# stepper_fw_bw_w_switch.net
KiCad netlist of a schematic drawn in EAGLE
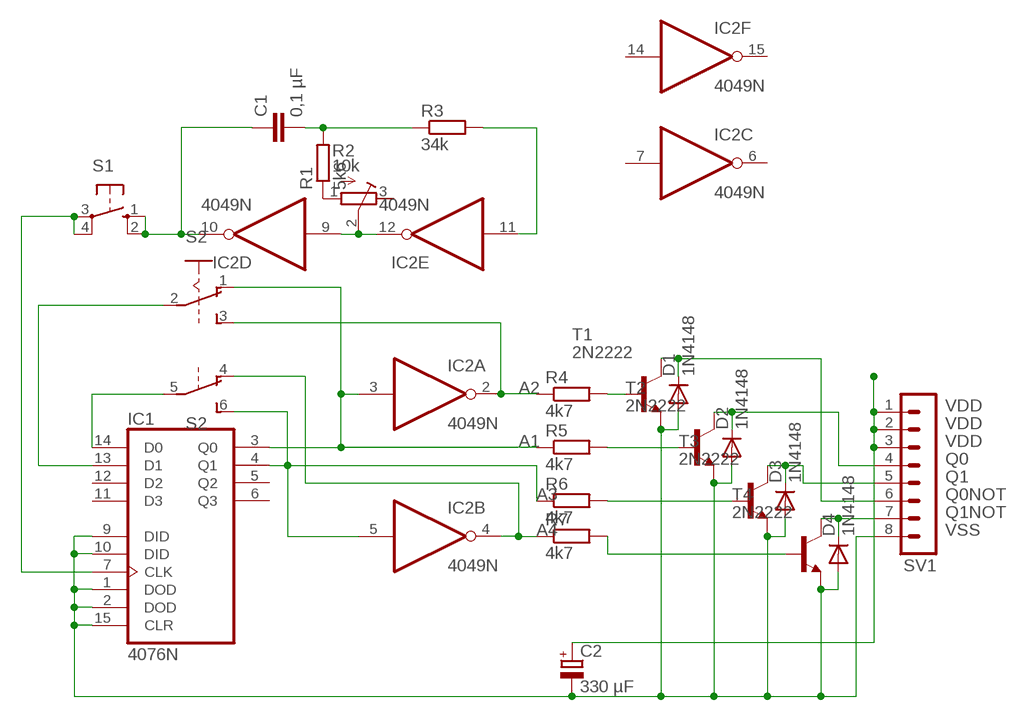
[diagram p0: schematic, sheet 1]

(export (version "E")
  (design (tool "Eeschema 10.0.6"))
  (components
    (comp (ref "C1")
      (value "0,1 µF")
      (footprint "eagle-import:C050-024X044")
      (libsource (lib "eagle-import") (part "C-EU050-024X044"))
    )
    (comp (ref "C2")
      (value "330 µF")
      (footprint "eagle-import:E2,5-5")
      (libsource (lib "eagle-import") (part "CPOL-EUE2.5-5"))
    )
    (comp (ref "D1")
      (value "1N4148")
      (footprint "eagle-import:D-2.5")
      (libsource (lib "eagle-import") (part "DIODE-D-2.5"))
    )
    (comp (ref "D2")
      (value "1N4148")
      (footprint "eagle-import:D-2.5")
      (libsource (lib "eagle-import") (part "DIODE-D-2.5"))
    )
    (comp (ref "D3")
      (value "1N4148")
      (footprint "eagle-import:D-2.5")
      (libsource (lib "eagle-import") (part "DIODE-D-2.5"))
    )
    (comp (ref "D4")
      (value "1N4148")
      (footprint "eagle-import:D-2.5")
      (libsource (lib "eagle-import") (part "DIODE-D-2.5"))
    )
    (comp (ref "IC1")
      (value "4076N")
      (footprint "eagle-import:DIL16")
      (libsource (lib "eagle-import") (part "4076N"))
    )
    (comp (ref "IC2")
      (value "4049N")
      (footprint "eagle-import:DIL16")
      (libsource (lib "eagle-import") (part "4049N"))
    )
    (comp (ref "R1")
      (value "5k6")
      (footprint "eagle-import:0207_10")
      (libsource (lib "eagle-import") (part "R-EU_0207/10"))
    )
    (comp (ref "R2")
      (value "10k")
      (footprint "eagle-import:RTRIM64W")
      (libsource (lib "eagle-import") (part "R-TRIMM64W"))
    )
    (comp (ref "R3")
      (value "34k")
      (footprint "eagle-import:0207_10")
      (libsource (lib "eagle-import") (part "R-EU_0207/10"))
    )
    (comp (ref "R4")
      (value "4k7")
      (footprint "eagle-import:0207_10")
      (libsource (lib "eagle-import") (part "R-EU_0207/10"))
    )
    (comp (ref "R5")
      (value "4k7")
      (footprint "eagle-import:0207_10")
      (libsource (lib "eagle-import") (part "R-EU_0207/10"))
    )
    (comp (ref "R6")
      (value "4k7")
      (footprint "eagle-import:0207_10")
      (libsource (lib "eagle-import") (part "R-EU_0207/10"))
    )
    (comp (ref "R7")
      (value "4k7")
      (footprint "eagle-import:0207_10")
      (libsource (lib "eagle-import") (part "R-EU_0207/10"))
    )
    (comp (ref "S1")
      (value "40-XX")
      (footprint "eagle-import:B3F-40XX")
      (fields (field (name "MF") "OMRON COMPONENTS USA") (field (name "MPN") "B3F-4000"))
      (libsource (lib "eagle-import") (part "40-XX"))
    )
    (comp (ref "S2")
      (value "A68-A31")
      (footprint "eagle-import:A68-A31")
      (libsource (lib "eagle-import") (part "A68-A31"))
    )
    (comp (ref "SV1")
      (value "MA08-1")
      (footprint "eagle-import:MA08-1")
      (libsource (lib "eagle-import") (part "MA08-1"))
    )
    (comp (ref "T1")
      (value "2N2222")
      (footprint "eagle-import:TO18")
      (libsource (lib "eagle-import") (part "2N2222"))
    )
    (comp (ref "T2")
      (value "2N2222")
      (footprint "eagle-import:TO18")
      (libsource (lib "eagle-import") (part "2N2222"))
    )
    (comp (ref "T3")
      (value "2N2222")
      (footprint "eagle-import:TO18")
      (libsource (lib "eagle-import") (part "2N2222"))
    )
    (comp (ref "T4")
      (value "2N2222")
      (footprint "eagle-import:TO18")
      (libsource (lib "eagle-import") (part "2N2222"))
    )
  )
  (nets
    (net (code "1") (name "/A1") (class "Default")
      (node (ref "IC1") (pin "3") (pinfunction "Q0_3") (pintype "output"))
      (node (ref "IC2") (pin "3") (pinfunction "I_3") (pintype "input"))
      (node (ref "R5") (pin "1") (pinfunction "1_1") (pintype "passive"))
      (node (ref "S2") (pin "1") (pinfunction "O_1") (pintype "passive"))
    )
    (net (code "2") (name "/A2") (class "Default")
      (node (ref "IC2") (pin "2") (pinfunction "O_2") (pintype "output"))
      (node (ref "R4") (pin "1") (pinfunction "1_1") (pintype "passive"))
      (node (ref "S2") (pin "3") (pinfunction "S_3") (pintype "passive"))
    )
    (net (code "3") (name "/A3") (class "Default")
      (node (ref "IC1") (pin "4") (pinfunction "Q1_4") (pintype "output"))
      (node (ref "IC2") (pin "5") (pinfunction "I_5") (pintype "input"))
      (node (ref "R6") (pin "1") (pinfunction "1_1") (pintype "passive"))
      (node (ref "S2") (pin "6") (pinfunction "S_6") (pintype "passive"))
    )
    (net (code "4") (name "/A4") (class "Default")
      (node (ref "IC2") (pin "4") (pinfunction "O_4") (pintype "output"))
      (node (ref "R7") (pin "1") (pinfunction "1_1") (pintype "passive"))
      (node (ref "S2") (pin "4") (pinfunction "O_4") (pintype "passive"))
    )
    (net (code "5") (name "/Q0") (class "Default")
      (node (ref "D2") (pin "C") (pinfunction "C_C") (pintype "passive"))
      (node (ref "SV1") (pin "4") (pinfunction "4_4") (pintype "passive"))
      (node (ref "T2") (pin "3") (pinfunction "C_3") (pintype "passive"))
    )
    (net (code "6") (name "/Q0NOT") (class "Default")
      (node (ref "D1") (pin "C") (pinfunction "C_C") (pintype "passive"))
      (node (ref "SV1") (pin "6") (pinfunction "6_6") (pintype "passive"))
      (node (ref "T1") (pin "3") (pinfunction "C_3") (pintype "passive"))
    )
    (net (code "7") (name "/Q1") (class "Default")
      (node (ref "D3") (pin "C") (pinfunction "C_C") (pintype "passive"))
      (node (ref "SV1") (pin "5") (pinfunction "5_5") (pintype "passive"))
      (node (ref "T3") (pin "3") (pinfunction "C_3") (pintype "passive"))
    )
    (net (code "8") (name "/Q1NOT") (class "Default")
      (node (ref "D4") (pin "C") (pinfunction "C_C") (pintype "passive"))
      (node (ref "SV1") (pin "7") (pinfunction "7_7") (pintype "passive"))
      (node (ref "T4") (pin "3") (pinfunction "C_3") (pintype "passive"))
    )
    (net (code "9") (name "/VDD") (class "Default")
      (node (ref "C2") (pin "+") (pinfunction "+_+") (pintype "passive"))
      (node (ref "SV1") (pin "1") (pinfunction "1_1") (pintype "passive"))
      (node (ref "SV1") (pin "2") (pinfunction "2_2") (pintype "passive"))
      (node (ref "SV1") (pin "3") (pinfunction "3_3") (pintype "passive"))
    )
    (net (code "10") (name "/VSS") (class "Default")
      (node (ref "C2") (pin "-") (pinfunction "-_-") (pintype "passive"))
      (node (ref "D1") (pin "A") (pinfunction "A_A") (pintype "passive"))
      (node (ref "D2") (pin "A") (pinfunction "A_A") (pintype "passive"))
      (node (ref "D3") (pin "A") (pinfunction "A_A") (pintype "passive"))
      (node (ref "D4") (pin "A") (pinfunction "A_A") (pintype "passive"))
      (node (ref "IC1") (pin "1") (pinfunction "DOD_1") (pintype "input"))
      (node (ref "IC1") (pin "10") (pinfunction "DID_10") (pintype "input"))
      (node (ref "IC1") (pin "15") (pinfunction "CLR_15") (pintype "input"))
      (node (ref "IC1") (pin "2") (pinfunction "DOD_2") (pintype "input"))
      (node (ref "IC1") (pin "9") (pinfunction "DID_9") (pintype "input"))
      (node (ref "SV1") (pin "8") (pinfunction "8_8") (pintype "passive"))
      (node (ref "T1") (pin "1") (pinfunction "E_1") (pintype "passive"))
      (node (ref "T2") (pin "1") (pinfunction "E_1") (pintype "passive"))
      (node (ref "T3") (pin "1") (pinfunction "E_1") (pintype "passive"))
      (node (ref "T4") (pin "1") (pinfunction "E_1") (pintype "passive"))
    )
    (net (code "11") (name "Net-(C1-Pad2)") (class "Default")
      (node (ref "C1") (pin "2") (pinfunction "2_2") (pintype "passive"))
      (node (ref "R1") (pin "2") (pinfunction "2_2") (pintype "passive"))
      (node (ref "R3") (pin "1") (pinfunction "1_1") (pintype "passive"))
    )
    (net (code "12") (name "Net-(IC1A-CLK)") (class "Default")
      (node (ref "IC1") (pin "7") (pinfunction "CLK_7") (pintype "input"))
      (node (ref "S1") (pin "3") (pinfunction "P_3") (pintype "passive"))
      (node (ref "S1") (pin "4") (pinfunction "P1_4") (pintype "passive"))
    )
    (net (code "13") (name "Net-(IC1A-D0)") (class "Default")
      (node (ref "IC1") (pin "14") (pinfunction "D0_14") (pintype "input"))
      (node (ref "S2") (pin "5") (pinfunction "P_5") (pintype "passive"))
    )
    (net (code "14") (name "Net-(IC1A-D1)") (class "Default")
      (node (ref "IC1") (pin "13") (pinfunction "D1_13") (pintype "input"))
      (node (ref "S2") (pin "2") (pinfunction "P_2") (pintype "passive"))
    )
    (net (code "15") (name "Net-(IC2D-I)") (class "Default")
      (node (ref "IC2") (pin "12") (pinfunction "O_12") (pintype "output"))
      (node (ref "IC2") (pin "9") (pinfunction "I_9") (pintype "input"))
      (node (ref "R2") (pin "2") (pinfunction "S_2") (pintype "passive"))
    )
    (net (code "16") (name "Net-(IC2D-O)") (class "Default")
      (node (ref "C1") (pin "1") (pinfunction "1_1") (pintype "passive"))
      (node (ref "IC2") (pin "10") (pinfunction "O_10") (pintype "output"))
      (node (ref "S1") (pin "1") (pinfunction "S_1") (pintype "passive"))
      (node (ref "S1") (pin "2") (pinfunction "S1_2") (pintype "passive"))
    )
    (net (code "17") (name "Net-(IC2E-I)") (class "Default")
      (node (ref "IC2") (pin "11") (pinfunction "I_11") (pintype "input"))
      (node (ref "R3") (pin "2") (pinfunction "2_2") (pintype "passive"))
    )
    (net (code "18") (name "Net-(R2-A)") (class "Default")
      (node (ref "R1") (pin "1") (pinfunction "1_1") (pintype "passive"))
      (node (ref "R2") (pin "1") (pinfunction "A_1") (pintype "passive"))
    )
    (net (code "19") (name "Net-(T1-B)") (class "Default")
      (node (ref "R4") (pin "2") (pinfunction "2_2") (pintype "passive"))
      (node (ref "T1") (pin "2") (pinfunction "B_2") (pintype "passive"))
    )
    (net (code "20") (name "Net-(T2-B)") (class "Default")
      (node (ref "R5") (pin "2") (pinfunction "2_2") (pintype "passive"))
      (node (ref "T2") (pin "2") (pinfunction "B_2") (pintype "passive"))
    )
    (net (code "21") (name "Net-(T3-B)") (class "Default")
      (node (ref "R6") (pin "2") (pinfunction "2_2") (pintype "passive"))
      (node (ref "T3") (pin "2") (pinfunction "B_2") (pintype "passive"))
    )
    (net (code "22") (name "Net-(T4-B)") (class "Default")
      (node (ref "R7") (pin "2") (pinfunction "2_2") (pintype "passive"))
      (node (ref "T4") (pin "2") (pinfunction "B_2") (pintype "passive"))
    )
    (net (code "23") (name "unconnected-(IC1A-D2-Pad12)") (class "Default")
      (node (ref "IC1") (pin "12") (pinfunction "D2_12") (pintype "input"))
    )
    (net (code "24") (name "unconnected-(IC1A-D3-Pad11)") (class "Default")
      (node (ref "IC1") (pin "11") (pinfunction "D3_11") (pintype "input"))
    )
    (net (code "25") (name "unconnected-(IC1A-Q2-Pad5)") (class "Default")
      (node (ref "IC1") (pin "5") (pinfunction "Q2_5") (pintype "output"))
    )
    (net (code "26") (name "unconnected-(IC1A-Q3-Pad6)") (class "Default")
      (node (ref "IC1") (pin "6") (pinfunction "Q3_6") (pintype "output"))
    )
    (net (code "27") (name "unconnected-(IC2C-I-Pad7)") (class "Default")
      (node (ref "IC2") (pin "7") (pinfunction "I_7") (pintype "input"))
    )
    (net (code "28") (name "unconnected-(IC2C-O-Pad6)") (class "Default")
      (node (ref "IC2") (pin "6") (pinfunction "O_6") (pintype "output"))
    )
    (net (code "29") (name "unconnected-(IC2F-I-Pad14)") (class "Default")
      (node (ref "IC2") (pin "14") (pinfunction "I_14") (pintype "input"))
    )
    (net (code "30") (name "unconnected-(IC2F-O-Pad15)") (class "Default")
      (node (ref "IC2") (pin "15") (pinfunction "O_15") (pintype "output"))
    )
    (net (code "31") (name "unconnected-(R2-E-Pad3)") (class "Default")
      (node (ref "R2") (pin "3") (pinfunction "E_3") (pintype "passive"))
    )
  )
)
